# Steam_Wand_Attachment_Controller.net
KiCad netlist of a schematic drawn in EasyEDA Pro
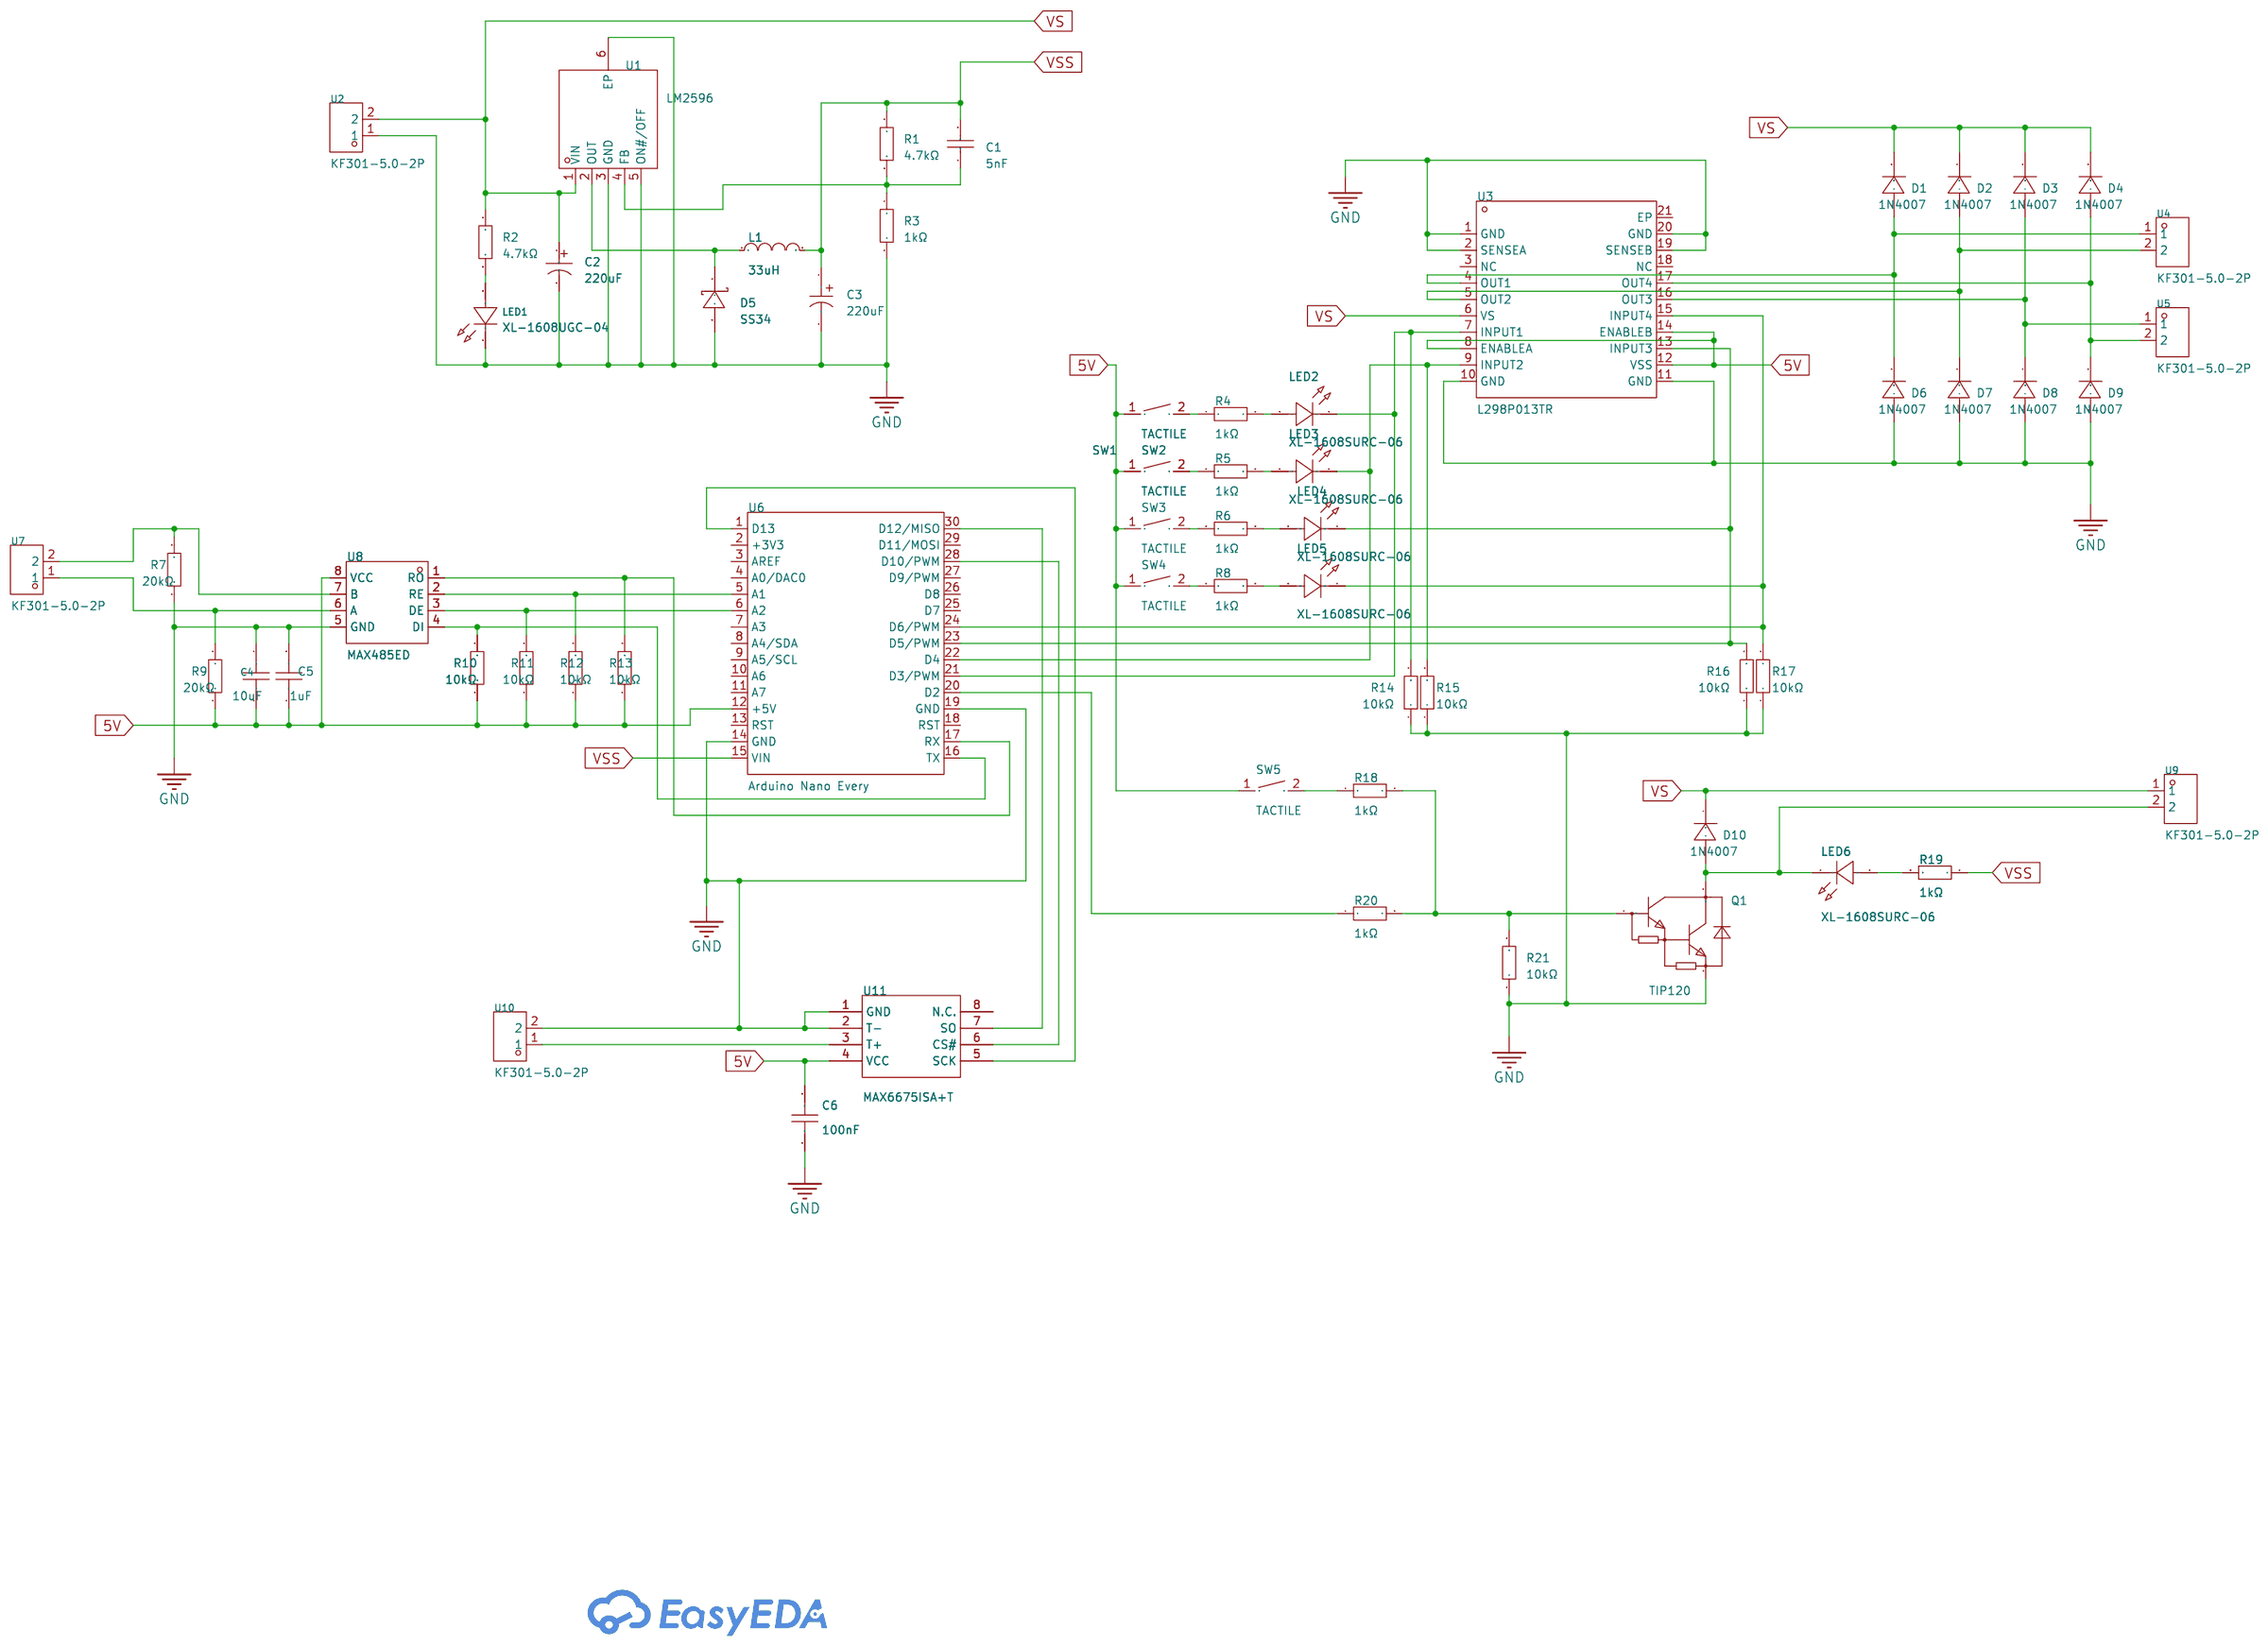
[diagram p0: schematic sheet]

(export (version "E")
  (design (tool "Eeschema 10.0.6"))
  (components
    (comp (ref "C1")
      (value "5nF")
      (footprint "easyedapro:C0805")
      (description "Capacitance:5nF Tolerance:±10% Tolerance:±10% Voltage Rating:50V Temperature Coefficient:X7R")
      (fields (field (name "Manufacturer Part") "0805B502K500NT") (field (name "Manufacturer") "FH(风华)"))
      (libsource (lib "easyedapro") (part "0805B502K500NT"))
    )
    (comp (ref "C2")
      (value "220uF")
      (footprint "easyedapro:CAP-SMD_BD10.0-L10.3-W10.3-LS11.3-FD")
      (fields (field (name "Manufacturer Part") "RVT1H221M1010") (field (name "Manufacturer") "ROQANG(容强)"))
      (libsource (lib "easyedapro") (part "RVT1H221M1010"))
    )
    (comp (ref "C3")
      (value "220uF")
      (footprint "easyedapro:CAP-SMD_BD6.3-L6.6-W6.6-LS7.4-FD")
      (fields (field (name "Manufacturer Part") "RVT1E221M0607") (field (name "Manufacturer") "ROQANG(容强)"))
      (libsource (lib "easyedapro") (part "RVT1E221M0607_C2918361"))
    )
    (comp (ref "C4")
      (value "10uF")
      (footprint "easyedapro:C0603")
      (fields
        (field (name "Manufacturer Part") "CL10A106MQ8NNNC")
        (field (name "Manufacturer") "SAMSUNG(三星)")
      )
      (libsource (lib "easyedapro") (part "CL10A106MQ8NNNC"))
    )
    (comp (ref "C5")
      (value "1uF")
      (footprint "easyedapro:C0603")
      (fields
        (field (name "Manufacturer Part") "CL10A105KB8NNNC")
        (field (name "Manufacturer") "SAMSUNG(三星)")
      )
      (libsource (lib "easyedapro") (part "CL10A105KB8NNNC"))
    )
    (comp (ref "C6")
      (value "100nF")
      (footprint "easyedapro:C0603")
      (description "Capacitance:100nF Tolerance:±10% Tolerance:±10% Voltage Rating:50V Temperature Coefficient:X7R")
      (fields
        (field (name "Manufacturer Part") "CC0603KRX7R9BB104")
        (field (name "Manufacturer") "YAGEO(国巨)")
      )
      (libsource (lib "easyedapro") (part "CC0603KRX7R9BB104"))
    )
    (comp (ref "D1")
      (value "1N4007")
      (footprint "easyedapro:SMAF_L3.5-W2.6-LS4.7-RD")
      (fields (field (name "Manufacturer") "HXY MOSFET(华轩阳电子)"))
      (libsource (lib "easyedapro") (part "1N4007_C2909975"))
    )
    (comp (ref "D2")
      (value "1N4007")
      (footprint "easyedapro:SMAF_L3.5-W2.6-LS4.7-RD")
      (fields (field (name "Manufacturer") "HXY MOSFET(华轩阳电子)"))
      (libsource (lib "easyedapro") (part "1N4007_C2909975"))
    )
    (comp (ref "D3")
      (value "1N4007")
      (footprint "easyedapro:SMAF_L3.5-W2.6-LS4.7-RD")
      (fields (field (name "Manufacturer") "HXY MOSFET(华轩阳电子)"))
      (libsource (lib "easyedapro") (part "1N4007_C2909975"))
    )
    (comp (ref "D4")
      (value "1N4007")
      (footprint "easyedapro:SMAF_L3.5-W2.6-LS4.7-RD")
      (fields (field (name "Manufacturer") "HXY MOSFET(华轩阳电子)"))
      (libsource (lib "easyedapro") (part "1N4007_C2909975"))
    )
    (comp (ref "D5")
      (value "SS34")
      (footprint "easyedapro:SMA_L4.3-W2.6-LS5.2-RD")
      (fields (field (name "Manufacturer") "MDD(辰达半导体)"))
      (libsource (lib "easyedapro") (part "SS34_C8678"))
    )
    (comp (ref "D6")
      (value "1N4007")
      (footprint "easyedapro:SMAF_L3.5-W2.6-LS4.7-RD")
      (fields (field (name "Manufacturer") "HXY MOSFET(华轩阳电子)"))
      (libsource (lib "easyedapro") (part "1N4007_C2909975"))
    )
    (comp (ref "D7")
      (value "1N4007")
      (footprint "easyedapro:SMAF_L3.5-W2.6-LS4.7-RD")
      (fields (field (name "Manufacturer") "HXY MOSFET(华轩阳电子)"))
      (libsource (lib "easyedapro") (part "1N4007_C2909975"))
    )
    (comp (ref "D8")
      (value "1N4007")
      (footprint "easyedapro:SMAF_L3.5-W2.6-LS4.7-RD")
      (fields (field (name "Manufacturer") "HXY MOSFET(华轩阳电子)"))
      (libsource (lib "easyedapro") (part "1N4007_C2909975"))
    )
    (comp (ref "D9")
      (value "1N4007")
      (footprint "easyedapro:SMAF_L3.5-W2.6-LS4.7-RD")
      (fields (field (name "Manufacturer") "HXY MOSFET(华轩阳电子)"))
      (libsource (lib "easyedapro") (part "1N4007_C2909975"))
    )
    (comp (ref "D10")
      (value "1N4007")
      (footprint "easyedapro:SMAF_L3.5-W2.6-LS4.7-RD")
      (fields (field (name "Manufacturer") "HXY MOSFET(华轩阳电子)"))
      (libsource (lib "easyedapro") (part "1N4007_C2909975"))
    )
    (comp (ref "L1")
      (value "33uH")
      (footprint "easyedapro:IND-SMD_L12.3-W12.3")
      (fields (field (name "Manufacturer Part") "SMDRI127-330MT") (field (name "Manufacturer") "SXN(顺翔诺)"))
      (libsource (lib "easyedapro") (part "SMDRI127-330MT"))
    )
    (comp (ref "LED1")
      (value "XL-1608UGC-04")
      (footprint "easyedapro:LED0603-RD_GREEN")
      (fields (field (name "Manufacturer") "XINGLIGHT(成兴光)"))
      (libsource (lib "easyedapro") (part "XL-1608UGC-04"))
    )
    (comp (ref "LED2")
      (value "XL-1608SURC-06")
      (footprint "easyedapro:LED0603-RD_RED")
      (fields (field (name "Manufacturer") "XINGLIGHT(成兴光)"))
      (libsource (lib "easyedapro") (part "XL-1608SURC-06"))
    )
    (comp (ref "LED3")
      (value "XL-1608SURC-06")
      (footprint "easyedapro:LED0603-RD_RED")
      (fields (field (name "Manufacturer") "XINGLIGHT(成兴光)"))
      (libsource (lib "easyedapro") (part "XL-1608SURC-06"))
    )
    (comp (ref "LED4")
      (value "XL-1608SURC-06")
      (footprint "easyedapro:LED0603-RD_RED")
      (fields (field (name "Manufacturer") "XINGLIGHT(成兴光)"))
      (libsource (lib "easyedapro") (part "XL-1608SURC-06"))
    )
    (comp (ref "LED5")
      (value "XL-1608SURC-06")
      (footprint "easyedapro:LED0603-RD_RED")
      (fields (field (name "Manufacturer") "XINGLIGHT(成兴光)"))
      (libsource (lib "easyedapro") (part "XL-1608SURC-06"))
    )
    (comp (ref "LED6")
      (value "XL-1608SURC-06")
      (footprint "easyedapro:LED0603-RD_RED")
      (fields (field (name "Manufacturer") "XINGLIGHT(成兴光)"))
      (libsource (lib "easyedapro") (part "XL-1608SURC-06"))
    )
    (comp (ref "Q1")
      (value "TIP120")
      (footprint "easyedapro:TO-220-3_L10.0-W4.5-P2.54-L")
      (fields (field (name "Manufacturer") "ST(意法半导体)"))
      (libsource (lib "easyedapro") (part "TIP120"))
    )
    (comp (ref "R1")
      (value "4.7kΩ")
      (footprint "easyedapro:R0603")
      (fields
        (field (name "Manufacturer Part") "0603WAF4701T5E")
        (field (name "Manufacturer") "UNI-ROYAL(厚声)")
      )
      (libsource (lib "easyedapro") (part "0603WAF4701T5E"))
    )
    (comp (ref "R2")
      (value "4.7kΩ")
      (footprint "easyedapro:R0603")
      (fields
        (field (name "Manufacturer Part") "0603WAF4701T5E")
        (field (name "Manufacturer") "UNI-ROYAL(厚声)")
      )
      (libsource (lib "easyedapro") (part "0603WAF4701T5E"))
    )
    (comp (ref "R3")
      (value "1kΩ")
      (footprint "easyedapro:R0603")
      (fields
        (field (name "Manufacturer Part") "0603WAF1001T5E")
        (field (name "Manufacturer") "UNI-ROYAL(厚声)")
      )
      (libsource (lib "easyedapro") (part "0603WAF1001T5E"))
    )
    (comp (ref "R4")
      (value "1kΩ")
      (footprint "easyedapro:R0603")
      (fields
        (field (name "Manufacturer Part") "0603WAF1001T5E")
        (field (name "Manufacturer") "UNI-ROYAL(厚声)")
      )
      (libsource (lib "easyedapro") (part "0603WAF1001T5E"))
    )
    (comp (ref "R5")
      (value "1kΩ")
      (footprint "easyedapro:R0603")
      (fields
        (field (name "Manufacturer Part") "0603WAF1001T5E")
        (field (name "Manufacturer") "UNI-ROYAL(厚声)")
      )
      (libsource (lib "easyedapro") (part "0603WAF1001T5E"))
    )
    (comp (ref "R6")
      (value "1kΩ")
      (footprint "easyedapro:R0603")
      (fields
        (field (name "Manufacturer Part") "0603WAF1001T5E")
        (field (name "Manufacturer") "UNI-ROYAL(厚声)")
      )
      (libsource (lib "easyedapro") (part "0603WAF1001T5E"))
    )
    (comp (ref "R7")
      (value "20kΩ")
      (footprint "easyedapro:R0603")
      (fields (field (name "Manufacturer Part") "SCR0603J20K") (field (name "Manufacturer") "VO(翔胜)"))
      (libsource (lib "easyedapro") (part "RC0603FR-0710KL"))
    )
    (comp (ref "R8")
      (value "1kΩ")
      (footprint "easyedapro:R0603")
      (fields
        (field (name "Manufacturer Part") "0603WAF1001T5E")
        (field (name "Manufacturer") "UNI-ROYAL(厚声)")
      )
      (libsource (lib "easyedapro") (part "0603WAF1001T5E"))
    )
    (comp (ref "R9")
      (value "20kΩ")
      (footprint "easyedapro:R0603")
      (fields (field (name "Manufacturer Part") "SCR0603J20K") (field (name "Manufacturer") "VO(翔胜)"))
      (libsource (lib "easyedapro") (part "RC0603FR-0710KL"))
    )
    (comp (ref "R10")
      (value "10kΩ")
      (footprint "easyedapro:R0603")
      (fields (field (name "Manufacturer Part") "RC0603FR-0710KL") (field (name "Manufacturer") "YAGEO(国巨)"))
      (libsource (lib "easyedapro") (part "RC0603FR-0710KL"))
    )
    (comp (ref "R11")
      (value "10kΩ")
      (footprint "easyedapro:R0603")
      (fields (field (name "Manufacturer Part") "RC0603FR-0710KL") (field (name "Manufacturer") "YAGEO(国巨)"))
      (libsource (lib "easyedapro") (part "RC0603FR-0710KL"))
    )
    (comp (ref "R12")
      (value "10kΩ")
      (footprint "easyedapro:R0603")
      (fields (field (name "Manufacturer Part") "RC0603FR-0710KL") (field (name "Manufacturer") "YAGEO(国巨)"))
      (libsource (lib "easyedapro") (part "RC0603FR-0710KL"))
    )
    (comp (ref "R13")
      (value "10kΩ")
      (footprint "easyedapro:R0603")
      (fields (field (name "Manufacturer Part") "RC0603FR-0710KL") (field (name "Manufacturer") "YAGEO(国巨)"))
      (libsource (lib "easyedapro") (part "RC0603FR-0710KL"))
    )
    (comp (ref "R14")
      (value "10kΩ")
      (footprint "easyedapro:R0603")
      (fields (field (name "Manufacturer Part") "RC0603FR-0710KL") (field (name "Manufacturer") "YAGEO(国巨)"))
      (libsource (lib "easyedapro") (part "RC0603FR-0710KL"))
    )
    (comp (ref "R15")
      (value "10kΩ")
      (footprint "easyedapro:R0603")
      (fields (field (name "Manufacturer Part") "RC0603FR-0710KL") (field (name "Manufacturer") "YAGEO(国巨)"))
      (libsource (lib "easyedapro") (part "RC0603FR-0710KL"))
    )
    (comp (ref "R16")
      (value "10kΩ")
      (footprint "easyedapro:R0603")
      (fields (field (name "Manufacturer Part") "RC0603FR-0710KL") (field (name "Manufacturer") "YAGEO(国巨)"))
      (libsource (lib "easyedapro") (part "RC0603FR-0710KL"))
    )
    (comp (ref "R17")
      (value "10kΩ")
      (footprint "easyedapro:R0603")
      (fields (field (name "Manufacturer Part") "RC0603FR-0710KL") (field (name "Manufacturer") "YAGEO(国巨)"))
      (libsource (lib "easyedapro") (part "RC0603FR-0710KL"))
    )
    (comp (ref "R18")
      (value "1kΩ")
      (footprint "easyedapro:R0603")
      (fields (field (name "Manufacturer Part") "z") (field (name "Manufacturer") "UNI-ROYAL(厚声)"))
      (libsource (lib "easyedapro") (part "0603WAF1001T5E"))
    )
    (comp (ref "R19")
      (value "1kΩ")
      (footprint "easyedapro:R0603")
      (fields
        (field (name "Manufacturer Part") "0603WAF1001T5E")
        (field (name "Manufacturer") "UNI-ROYAL(厚声)")
      )
      (libsource (lib "easyedapro") (part "0603WAF1001T5E"))
    )
    (comp (ref "R20")
      (value "1kΩ")
      (footprint "easyedapro:R0603")
      (fields
        (field (name "Manufacturer Part") "0603WAF1001T5E")
        (field (name "Manufacturer") "UNI-ROYAL(厚声)")
      )
      (libsource (lib "easyedapro") (part "0603WAF1001T5E"))
    )
    (comp (ref "R21")
      (value "10kΩ")
      (footprint "easyedapro:R0603")
      (fields (field (name "Manufacturer Part") "RC0603FR-0710KL") (field (name "Manufacturer") "YAGEO(国巨)"))
      (libsource (lib "easyedapro") (part "RC0603FR-0710KL"))
    )
    (comp (ref "SW1")
      (value "TACTILE")
      (footprint "easyedapro:KEY-SMD_L4.0-W3.0-LS4.9-1")
      (fields (field (name "Manufacturer") "hanxia(韩下)"))
      (libsource (lib "easyedapro") (part "HX 3X4X2-2P-1.6N TACTILE SWITCH"))
    )
    (comp (ref "SW2")
      (value "TACTILE")
      (footprint "easyedapro:KEY-SMD_L4.0-W3.0-LS4.9-1")
      (fields (field (name "Manufacturer") "hanxia(韩下)"))
      (libsource (lib "easyedapro") (part "HX 3X4X2-2P-1.6N TACTILE SWITCH"))
    )
    (comp (ref "SW3")
      (value "TACTILE")
      (footprint "easyedapro:KEY-SMD_L4.0-W3.0-LS4.9-1")
      (fields (field (name "Manufacturer") "hanxia(韩下)"))
      (libsource (lib "easyedapro") (part "HX 3X4X2-2P-1.6N TACTILE SWITCH"))
    )
    (comp (ref "SW4")
      (value "TACTILE")
      (footprint "easyedapro:KEY-SMD_L4.0-W3.0-LS4.9-1")
      (fields (field (name "Manufacturer") "hanxia(韩下)"))
      (libsource (lib "easyedapro") (part "HX 3X4X2-2P-1.6N TACTILE SWITCH"))
    )
    (comp (ref "SW5")
      (value "TACTILE")
      (footprint "easyedapro:KEY-SMD_L4.0-W3.0-LS4.9-1")
      (fields (field (name "Manufacturer") "hanxia(韩下)"))
      (libsource (lib "easyedapro") (part "HX 3X4X2-2P-1.6N TACTILE SWITCH"))
    )
    (comp (ref "U1")
      (value "LM2596")
      (footprint "easyedapro:TO-263-5_L10.2-W8.9-P1.70-BR")
      (fields (field (name "Manufacturer") "UMW(友台半导体)"))
      (libsource (lib "easyedapro") (part "LM2596S-5.0"))
    )
    (comp (ref "U2")
      (value "KF301-5.0-2P")
      (footprint "easyedapro:CONN-TH_P5.00_KF301-5.0-2P")
      (fields (field (name "Manufacturer") "KEFA(科发)"))
      (libsource (lib "easyedapro") (part "KF301-5.0-2P"))
    )
    (comp (ref "U3")
      (value "L298P013TR")
      (footprint "easyedapro:POWERSO20_L15.9-W11.0-P1.27-LS14.2-BL-EP")
      (fields (field (name "Manufacturer") "ST(意法半导体)"))
      (libsource (lib "easyedapro") (part "L298P013TR"))
    )
    (comp (ref "U4")
      (value "KF301-5.0-2P")
      (footprint "easyedapro:CONN-TH_P5.00_KF301-5.0-2P")
      (fields (field (name "Manufacturer") "KEFA(科发)"))
      (libsource (lib "easyedapro") (part "KF301-5.0-2P"))
    )
    (comp (ref "U5")
      (value "KF301-5.0-2P")
      (footprint "easyedapro:CONN-TH_P5.00_KF301-5.0-2P")
      (fields (field (name "Manufacturer") "KEFA(科发)"))
      (libsource (lib "easyedapro") (part "KF301-5.0-2P"))
    )
    (comp (ref "U6")
      (value "Arduino Nano Every")
      (footprint "easyedapro:MOD-TH_ABX00028")
      (fields (field (name "Manufacturer") "arduino"))
      (libsource (lib "easyedapro") (part "ABX00028"))
    )
    (comp (ref "U7")
      (value "KF301-5.0-2P")
      (footprint "easyedapro:CONN-TH_P5.00_KF301-5.0-2P")
      (fields (field (name "Manufacturer") "KEFA(科发)"))
      (libsource (lib "easyedapro") (part "KF301-5.0-2P"))
    )
    (comp (ref "U8")
      (value "MAX485ED")
      (footprint "easyedapro:SOP-8_L4.9-W3.9-P1.27-LS6.0-BL")
      (fields (field (name "Manufacturer") "HTC"))
      (libsource (lib "easyedapro") (part "MAX485ED"))
    )
    (comp (ref "U9")
      (value "KF301-5.0-2P")
      (footprint "easyedapro:CONN-TH_P5.00_KF301-5.0-2P")
      (fields (field (name "Manufacturer") "KEFA(科发)"))
      (libsource (lib "easyedapro") (part "KF301-5.0-2P"))
    )
    (comp (ref "U10")
      (value "KF301-5.0-2P")
      (footprint "easyedapro:CONN-TH_P5.00_KF301-5.0-2P")
      (fields (field (name "Manufacturer") "KEFA(科发)"))
      (libsource (lib "easyedapro") (part "KF301-5.0-2P"))
    )
    (comp (ref "U11")
      (value "MAX6675ISA+T")
      (footprint "easyedapro:SOIC-8_L5.0-W4.0-P1.27-LS6.0-BL")
      (description "Supply Current: Operating Temperature: Type: Input Type:- Output Type:-")
      (fields (field (name "Manufacturer") "MAXIM(美信)"))
      (libsource (lib "easyedapro") (part "MAX6675ISA+T"))
    )
  )
  (nets
    (net (code "1") (name "5V") (class "Default")
      (node (ref "C4") (pin "1") (pinfunction "1_1") (pintype "input"))
      (node (ref "C5") (pin "1") (pinfunction "1_1") (pintype "unspecified"))
      (node (ref "C6") (pin "1") (pinfunction "1_1") (pintype "unspecified"))
      (node (ref "R10") (pin "1") (pinfunction "1_1") (pintype "input"))
      (node (ref "R11") (pin "1") (pinfunction "1_1") (pintype "input"))
      (node (ref "R12") (pin "1") (pinfunction "1_1") (pintype "input"))
      (node (ref "R13") (pin "1") (pinfunction "1_1") (pintype "input"))
      (node (ref "R9") (pin "1") (pinfunction "1_1") (pintype "input"))
      (node (ref "SW1") (pin "1") (pinfunction "1_1") (pintype "unspecified"))
      (node (ref "SW2") (pin "1") (pinfunction "1_1") (pintype "unspecified"))
      (node (ref "SW3") (pin "1") (pinfunction "1_1") (pintype "unspecified"))
      (node (ref "SW4") (pin "1") (pinfunction "1_1") (pintype "unspecified"))
      (node (ref "SW5") (pin "1") (pinfunction "1_1") (pintype "unspecified"))
      (node (ref "U11") (pin "4") (pinfunction "VCC_4") (pintype "input"))
      (node (ref "U3") (pin "12") (pinfunction "VSS_12") (pintype "unspecified"))
      (node (ref "U3") (pin "14") (pinfunction "ENABLEB_14") (pintype "unspecified"))
      (node (ref "U3") (pin "8") (pinfunction "ENABLEA_8") (pintype "unspecified"))
      (node (ref "U6") (pin "12") (pinfunction "+5V_12") (pintype "unspecified"))
      (node (ref "U8") (pin "8") (pinfunction "VCC_8") (pintype "unspecified"))
    )
    (net (code "2") (name "GND") (class "Default")
      (node (ref "C2") (pin "2") (pinfunction "2_2") (pintype "input"))
      (node (ref "C3") (pin "2") (pinfunction "2_2") (pintype "input"))
      (node (ref "C4") (pin "2") (pinfunction "2_2") (pintype "input"))
      (node (ref "C5") (pin "2") (pinfunction "2_2") (pintype "unspecified"))
      (node (ref "C6") (pin "2") (pinfunction "2_2") (pintype "unspecified"))
      (node (ref "D5") (pin "2") (pinfunction "A_2") (pintype "unspecified"))
      (node (ref "D6") (pin "2") (pinfunction "A_2") (pintype "unspecified"))
      (node (ref "D7") (pin "2") (pinfunction "A_2") (pintype "unspecified"))
      (node (ref "D8") (pin "2") (pinfunction "A_2") (pintype "unspecified"))
      (node (ref "D9") (pin "2") (pinfunction "A_2") (pintype "unspecified"))
      (node (ref "LED1") (pin "1") (pinfunction "K_1") (pintype "input"))
      (node (ref "Q1") (pin "3") (pinfunction "E_3") (pintype "input"))
      (node (ref "R14") (pin "1") (pinfunction "1_1") (pintype "input"))
      (node (ref "R15") (pin "1") (pinfunction "1_1") (pintype "input"))
      (node (ref "R16") (pin "1") (pinfunction "1_1") (pintype "input"))
      (node (ref "R17") (pin "1") (pinfunction "1_1") (pintype "input"))
      (node (ref "R21") (pin "1") (pinfunction "1_1") (pintype "input"))
      (node (ref "R3") (pin "2") (pinfunction "2_2") (pintype "input"))
      (node (ref "R7") (pin "1") (pinfunction "1_1") (pintype "input"))
      (node (ref "U1") (pin "3") (pinfunction "GND_3") (pintype "unspecified"))
      (node (ref "U1") (pin "5") (pinfunction "ON#/OFF_5") (pintype "unspecified"))
      (node (ref "U1") (pin "6") (pinfunction "EP_6") (pintype "unspecified"))
      (node (ref "U10") (pin "2") (pinfunction "2_2") (pintype "input"))
      (node (ref "U11") (pin "1") (pinfunction "GND_1") (pintype "input"))
      (node (ref "U11") (pin "2") (pinfunction "T-_2") (pintype "input"))
      (node (ref "U2") (pin "1") (pinfunction "1_1") (pintype "input"))
      (node (ref "U3") (pin "1") (pinfunction "GND_1") (pintype "unspecified"))
      (node (ref "U3") (pin "10") (pinfunction "GND_10") (pintype "unspecified"))
      (node (ref "U3") (pin "11") (pinfunction "GND_11") (pintype "unspecified"))
      (node (ref "U3") (pin "19") (pinfunction "SENSEB_19") (pintype "unspecified"))
      (node (ref "U3") (pin "2") (pinfunction "SENSEA_2") (pintype "unspecified"))
      (node (ref "U3") (pin "20") (pinfunction "GND_20") (pintype "unspecified"))
      (node (ref "U6") (pin "14") (pinfunction "GND_14") (pintype "unspecified"))
      (node (ref "U6") (pin "19") (pinfunction "GND_19") (pintype "unspecified"))
      (node (ref "U8") (pin "5") (pinfunction "GND_5") (pintype "unspecified"))
    )
    (net (code "3") (name "Net-(D1-A)") (class "Default")
      (node (ref "D1") (pin "2") (pinfunction "A_2") (pintype "unspecified"))
      (node (ref "D6") (pin "1") (pinfunction "C_1") (pintype "unspecified"))
      (node (ref "U3") (pin "4") (pinfunction "OUT1_4") (pintype "unspecified"))
      (node (ref "U4") (pin "1") (pinfunction "1_1") (pintype "input"))
    )
    (net (code "4") (name "Net-(D2-A)") (class "Default")
      (node (ref "D2") (pin "2") (pinfunction "A_2") (pintype "unspecified"))
      (node (ref "D7") (pin "1") (pinfunction "C_1") (pintype "unspecified"))
      (node (ref "U3") (pin "5") (pinfunction "OUT2_5") (pintype "unspecified"))
      (node (ref "U4") (pin "2") (pinfunction "2_2") (pintype "input"))
    )
    (net (code "5") (name "Net-(D3-A)") (class "Default")
      (node (ref "D3") (pin "2") (pinfunction "A_2") (pintype "unspecified"))
      (node (ref "D8") (pin "1") (pinfunction "C_1") (pintype "unspecified"))
      (node (ref "U3") (pin "16") (pinfunction "OUT3_16") (pintype "unspecified"))
      (node (ref "U5") (pin "1") (pinfunction "1_1") (pintype "input"))
    )
    (net (code "6") (name "Net-(D4-A)") (class "Default")
      (node (ref "D4") (pin "2") (pinfunction "A_2") (pintype "unspecified"))
      (node (ref "D9") (pin "1") (pinfunction "C_1") (pintype "unspecified"))
      (node (ref "U3") (pin "17") (pinfunction "OUT4_17") (pintype "unspecified"))
      (node (ref "U5") (pin "2") (pinfunction "2_2") (pintype "input"))
    )
    (net (code "7") (name "Net-(D5-K)") (class "Default")
      (node (ref "D5") (pin "1") (pinfunction "K_1") (pintype "unspecified"))
      (node (ref "L1") (pin "1") (pinfunction "1_1") (pintype "unspecified"))
      (node (ref "U1") (pin "2") (pinfunction "OUT_2") (pintype "unspecified"))
    )
    (net (code "8") (name "Net-(D10-A)") (class "Default")
      (node (ref "D10") (pin "2") (pinfunction "A_2") (pintype "unspecified"))
      (node (ref "LED6") (pin "1") (pinfunction "K_1") (pintype "unspecified"))
      (node (ref "Q1") (pin "2") (pinfunction "C_2") (pintype "input"))
      (node (ref "U9") (pin "2") (pinfunction "2_2") (pintype "input"))
    )
    (net (code "9") (name "Net-(LED1-A)") (class "Default")
      (node (ref "LED1") (pin "2") (pinfunction "A_2") (pintype "input"))
      (node (ref "R2") (pin "2") (pinfunction "2_2") (pintype "input"))
    )
    (net (code "10") (name "Net-(LED2-A)") (class "Default")
      (node (ref "LED2") (pin "2") (pinfunction "A_2") (pintype "unspecified"))
      (node (ref "R4") (pin "2") (pinfunction "2_2") (pintype "input"))
    )
    (net (code "11") (name "Net-(LED2-K)") (class "Default")
      (node (ref "LED2") (pin "1") (pinfunction "K_1") (pintype "unspecified"))
      (node (ref "R14") (pin "2") (pinfunction "2_2") (pintype "input"))
      (node (ref "U3") (pin "7") (pinfunction "INPUT1_7") (pintype "unspecified"))
      (node (ref "U6") (pin "21") (pinfunction "D3/PWM_21") (pintype "unspecified"))
    )
    (net (code "12") (name "Net-(LED3-A)") (class "Default")
      (node (ref "LED3") (pin "2") (pinfunction "A_2") (pintype "unspecified"))
      (node (ref "R5") (pin "2") (pinfunction "2_2") (pintype "input"))
    )
    (net (code "13") (name "Net-(LED3-K)") (class "Default")
      (node (ref "LED3") (pin "1") (pinfunction "K_1") (pintype "unspecified"))
      (node (ref "R15") (pin "2") (pinfunction "2_2") (pintype "input"))
      (node (ref "U3") (pin "9") (pinfunction "INPUT2_9") (pintype "unspecified"))
      (node (ref "U6") (pin "22") (pinfunction "D4_22") (pintype "unspecified"))
    )
    (net (code "14") (name "Net-(LED4-A)") (class "Default")
      (node (ref "LED4") (pin "2") (pinfunction "A_2") (pintype "unspecified"))
      (node (ref "R6") (pin "2") (pinfunction "2_2") (pintype "input"))
    )
    (net (code "15") (name "Net-(LED4-K)") (class "Default")
      (node (ref "LED4") (pin "1") (pinfunction "K_1") (pintype "unspecified"))
      (node (ref "R16") (pin "2") (pinfunction "2_2") (pintype "input"))
      (node (ref "U3") (pin "13") (pinfunction "INPUT3_13") (pintype "unspecified"))
      (node (ref "U6") (pin "23") (pinfunction "D5/PWM_23") (pintype "unspecified"))
    )
    (net (code "16") (name "Net-(LED5-A)") (class "Default")
      (node (ref "LED5") (pin "2") (pinfunction "A_2") (pintype "unspecified"))
      (node (ref "R8") (pin "2") (pinfunction "2_2") (pintype "input"))
    )
    (net (code "17") (name "Net-(LED5-K)") (class "Default")
      (node (ref "LED5") (pin "1") (pinfunction "K_1") (pintype "unspecified"))
      (node (ref "R17") (pin "2") (pinfunction "2_2") (pintype "input"))
      (node (ref "U3") (pin "15") (pinfunction "INPUT4_15") (pintype "unspecified"))
      (node (ref "U6") (pin "24") (pinfunction "D6/PWM_24") (pintype "unspecified"))
    )
    (net (code "18") (name "Net-(LED6-A)") (class "Default")
      (node (ref "LED6") (pin "2") (pinfunction "A_2") (pintype "unspecified"))
      (node (ref "R19") (pin "2") (pinfunction "2_2") (pintype "input"))
    )
    (net (code "19") (name "Net-(Q1-B)") (class "Default")
      (node (ref "Q1") (pin "1") (pinfunction "B_1") (pintype "input"))
      (node (ref "R18") (pin "2") (pinfunction "2_2") (pintype "input"))
      (node (ref "R20") (pin "2") (pinfunction "2_2") (pintype "input"))
      (node (ref "R21") (pin "2") (pinfunction "2_2") (pintype "input"))
    )
    (net (code "20") (name "Net-(R4-Pad1)") (class "Default")
      (node (ref "R4") (pin "1") (pinfunction "1_1") (pintype "input"))
      (node (ref "SW1") (pin "2") (pinfunction "2_2") (pintype "unspecified"))
    )
    (net (code "21") (name "Net-(R5-Pad1)") (class "Default")
      (node (ref "R5") (pin "1") (pinfunction "1_1") (pintype "input"))
      (node (ref "SW2") (pin "2") (pinfunction "2_2") (pintype "unspecified"))
    )
    (net (code "22") (name "Net-(R6-Pad1)") (class "Default")
      (node (ref "R6") (pin "1") (pinfunction "1_1") (pintype "input"))
      (node (ref "SW3") (pin "2") (pinfunction "2_2") (pintype "unspecified"))
    )
    (net (code "23") (name "Net-(R8-Pad1)") (class "Default")
      (node (ref "R8") (pin "1") (pinfunction "1_1") (pintype "input"))
      (node (ref "SW4") (pin "2") (pinfunction "2_2") (pintype "unspecified"))
    )
    (net (code "24") (name "Net-(R18-Pad1)") (class "Default")
      (node (ref "R18") (pin "1") (pinfunction "1_1") (pintype "input"))
      (node (ref "SW5") (pin "2") (pinfunction "2_2") (pintype "unspecified"))
    )
    (net (code "25") (name "Net-(U1-FB)") (class "Default")
      (node (ref "C1") (pin "1") (pinfunction "1_1") (pintype "input"))
      (node (ref "R1") (pin "2") (pinfunction "2_2") (pintype "input"))
      (node (ref "R3") (pin "1") (pinfunction "1_1") (pintype "input"))
      (node (ref "U1") (pin "4") (pinfunction "FB_4") (pintype "unspecified"))
    )
    (net (code "26") (name "Net-(U6-A1)") (class "Default")
      (node (ref "R12") (pin "2") (pinfunction "2_2") (pintype "input"))
      (node (ref "U6") (pin "5") (pinfunction "A1_5") (pintype "unspecified"))
      (node (ref "U8") (pin "2") (pinfunction "RE_2") (pintype "unspecified"))
    )
    (net (code "27") (name "Net-(U6-A2)") (class "Default")
      (node (ref "R11") (pin "2") (pinfunction "2_2") (pintype "input"))
      (node (ref "U6") (pin "6") (pinfunction "A2_6") (pintype "unspecified"))
      (node (ref "U8") (pin "3") (pinfunction "DE_3") (pintype "unspecified"))
    )
    (net (code "28") (name "Net-(U6-D2)") (class "Default")
      (node (ref "R20") (pin "1") (pinfunction "1_1") (pintype "input"))
      (node (ref "U6") (pin "20") (pinfunction "D2_20") (pintype "unspecified"))
    )
    (net (code "29") (name "Net-(U6-RX)") (class "Default")
      (node (ref "R13") (pin "2") (pinfunction "2_2") (pintype "input"))
      (node (ref "U6") (pin "17") (pinfunction "RX_17") (pintype "unspecified"))
      (node (ref "U8") (pin "1") (pinfunction "RO_1") (pintype "unspecified"))
    )
    (net (code "30") (name "Net-(U6-TX)") (class "Default")
      (node (ref "R10") (pin "2") (pinfunction "2_2") (pintype "input"))
      (node (ref "U6") (pin "16") (pinfunction "TX_16") (pintype "unspecified"))
      (node (ref "U8") (pin "4") (pinfunction "DI_4") (pintype "unspecified"))
    )
    (net (code "31") (name "Net-(U8-A)") (class "Default")
      (node (ref "R9") (pin "2") (pinfunction "2_2") (pintype "input"))
      (node (ref "U7") (pin "1") (pinfunction "1_1") (pintype "input"))
      (node (ref "U8") (pin "6") (pinfunction "A_6") (pintype "unspecified"))
    )
    (net (code "32") (name "Net-(U8-B)") (class "Default")
      (node (ref "R7") (pin "2") (pinfunction "2_2") (pintype "input"))
      (node (ref "U7") (pin "2") (pinfunction "2_2") (pintype "input"))
      (node (ref "U8") (pin "7") (pinfunction "B_7") (pintype "unspecified"))
    )
    (net (code "33") (name "Net-(U11-CS#)") (class "Default")
      (node (ref "U11") (pin "6") (pinfunction "CS#_6") (pintype "input"))
      (node (ref "U6") (pin "28") (pinfunction "D10/PWM_28") (pintype "unspecified"))
    )
    (net (code "34") (name "Net-(U11-SCK)") (class "Default")
      (node (ref "U11") (pin "5") (pinfunction "SCK_5") (pintype "input"))
      (node (ref "U6") (pin "1") (pinfunction "D13_1") (pintype "unspecified"))
    )
    (net (code "35") (name "Net-(U11-SO)") (class "Default")
      (node (ref "U11") (pin "7") (pinfunction "SO_7") (pintype "input"))
      (node (ref "U6") (pin "30") (pinfunction "D12/MISO_30") (pintype "unspecified"))
    )
    (net (code "36") (name "Net-(U11-T+)") (class "Default")
      (node (ref "U10") (pin "1") (pinfunction "1_1") (pintype "input"))
      (node (ref "U11") (pin "3") (pinfunction "T+_3") (pintype "input"))
    )
    (net (code "37") (name "VS") (class "Default")
      (node (ref "C2") (pin "1") (pinfunction "1_1") (pintype "input"))
      (node (ref "D1") (pin "1") (pinfunction "C_1") (pintype "unspecified"))
      (node (ref "D10") (pin "1") (pinfunction "C_1") (pintype "unspecified"))
      (node (ref "D2") (pin "1") (pinfunction "C_1") (pintype "unspecified"))
      (node (ref "D3") (pin "1") (pinfunction "C_1") (pintype "unspecified"))
      (node (ref "D4") (pin "1") (pinfunction "C_1") (pintype "unspecified"))
      (node (ref "R2") (pin "1") (pinfunction "1_1") (pintype "input"))
      (node (ref "U1") (pin "1") (pinfunction "VIN_1") (pintype "unspecified"))
      (node (ref "U2") (pin "2") (pinfunction "2_2") (pintype "input"))
      (node (ref "U3") (pin "6") (pinfunction "VS_6") (pintype "unspecified"))
      (node (ref "U9") (pin "1") (pinfunction "1_1") (pintype "input"))
    )
    (net (code "38") (name "VSS") (class "Default")
      (node (ref "C1") (pin "2") (pinfunction "2_2") (pintype "input"))
      (node (ref "C3") (pin "1") (pinfunction "1_1") (pintype "input"))
      (node (ref "L1") (pin "2") (pinfunction "2_2") (pintype "unspecified"))
      (node (ref "R1") (pin "1") (pinfunction "1_1") (pintype "input"))
      (node (ref "R19") (pin "1") (pinfunction "1_1") (pintype "input"))
      (node (ref "U6") (pin "15") (pinfunction "VIN_15") (pintype "unspecified"))
    )
    (net (code "39") (name "unconnected-(U3-EP-Pad21)") (class "Default")
      (node (ref "U3") (pin "21") (pinfunction "EP_21") (pintype "unspecified"))
    )
    (net (code "40") (name "unconnected-(U3-NC-Pad3)") (class "Default")
      (node (ref "U3") (pin "3") (pinfunction "NC_3") (pintype "unspecified"))
    )
    (net (code "41") (name "unconnected-(U3-NC-Pad18)") (class "Default")
      (node (ref "U3") (pin "18") (pinfunction "NC_18") (pintype "unspecified"))
    )
    (net (code "42") (name "unconnected-(U6-+3V3-Pad2)") (class "Default")
      (node (ref "U6") (pin "2") (pinfunction "+3V3_2") (pintype "unspecified"))
    )
    (net (code "43") (name "unconnected-(U6-A0{slash}DAC0-Pad4)") (class "Default")
      (node (ref "U6") (pin "4") (pinfunction "A0/DAC0_4") (pintype "unspecified"))
    )
    (net (code "44") (name "unconnected-(U6-A3-Pad7)") (class "Default")
      (node (ref "U6") (pin "7") (pinfunction "A3_7") (pintype "unspecified"))
    )
    (net (code "45") (name "unconnected-(U6-A4{slash}SDA-Pad8)") (class "Default")
      (node (ref "U6") (pin "8") (pinfunction "A4/SDA_8") (pintype "unspecified"))
    )
    (net (code "46") (name "unconnected-(U6-A5{slash}SCL-Pad9)") (class "Default")
      (node (ref "U6") (pin "9") (pinfunction "A5/SCL_9") (pintype "unspecified"))
    )
    (net (code "47") (name "unconnected-(U6-A6-Pad10)") (class "Default")
      (node (ref "U6") (pin "10") (pinfunction "A6_10") (pintype "unspecified"))
    )
    (net (code "48") (name "unconnected-(U6-A7-Pad11)") (class "Default")
      (node (ref "U6") (pin "11") (pinfunction "A7_11") (pintype "unspecified"))
    )
    (net (code "49") (name "unconnected-(U6-AREF-Pad3)") (class "Default")
      (node (ref "U6") (pin "3") (pinfunction "AREF_3") (pintype "unspecified"))
    )
    (net (code "50") (name "unconnected-(U6-D7-Pad25)") (class "Default")
      (node (ref "U6") (pin "25") (pinfunction "D7_25") (pintype "unspecified"))
    )
    (net (code "51") (name "unconnected-(U6-D8-Pad26)") (class "Default")
      (node (ref "U6") (pin "26") (pinfunction "D8_26") (pintype "unspecified"))
    )
    (net (code "52") (name "unconnected-(U6-D9{slash}PWM-Pad27)") (class "Default")
      (node (ref "U6") (pin "27") (pinfunction "D9/PWM_27") (pintype "unspecified"))
    )
    (net (code "53") (name "unconnected-(U6-D11{slash}MOSI-Pad29)") (class "Default")
      (node (ref "U6") (pin "29") (pinfunction "D11/MOSI_29") (pintype "unspecified"))
    )
    (net (code "54") (name "unconnected-(U6-RST-Pad13)") (class "Default")
      (node (ref "U6") (pin "13") (pinfunction "RST_13") (pintype "unspecified"))
    )
    (net (code "55") (name "unconnected-(U6-RST-Pad18)") (class "Default")
      (node (ref "U6") (pin "18") (pinfunction "RST_18") (pintype "unspecified"))
    )
    (net (code "56") (name "unconnected-(U11-N.C.-Pad8)") (class "Default")
      (node (ref "U11") (pin "8") (pinfunction "N.C._8") (pintype "input"))
    )
  )
)
